# DAC.net
KiCad netlist of a schematic drawn in Altium Designer
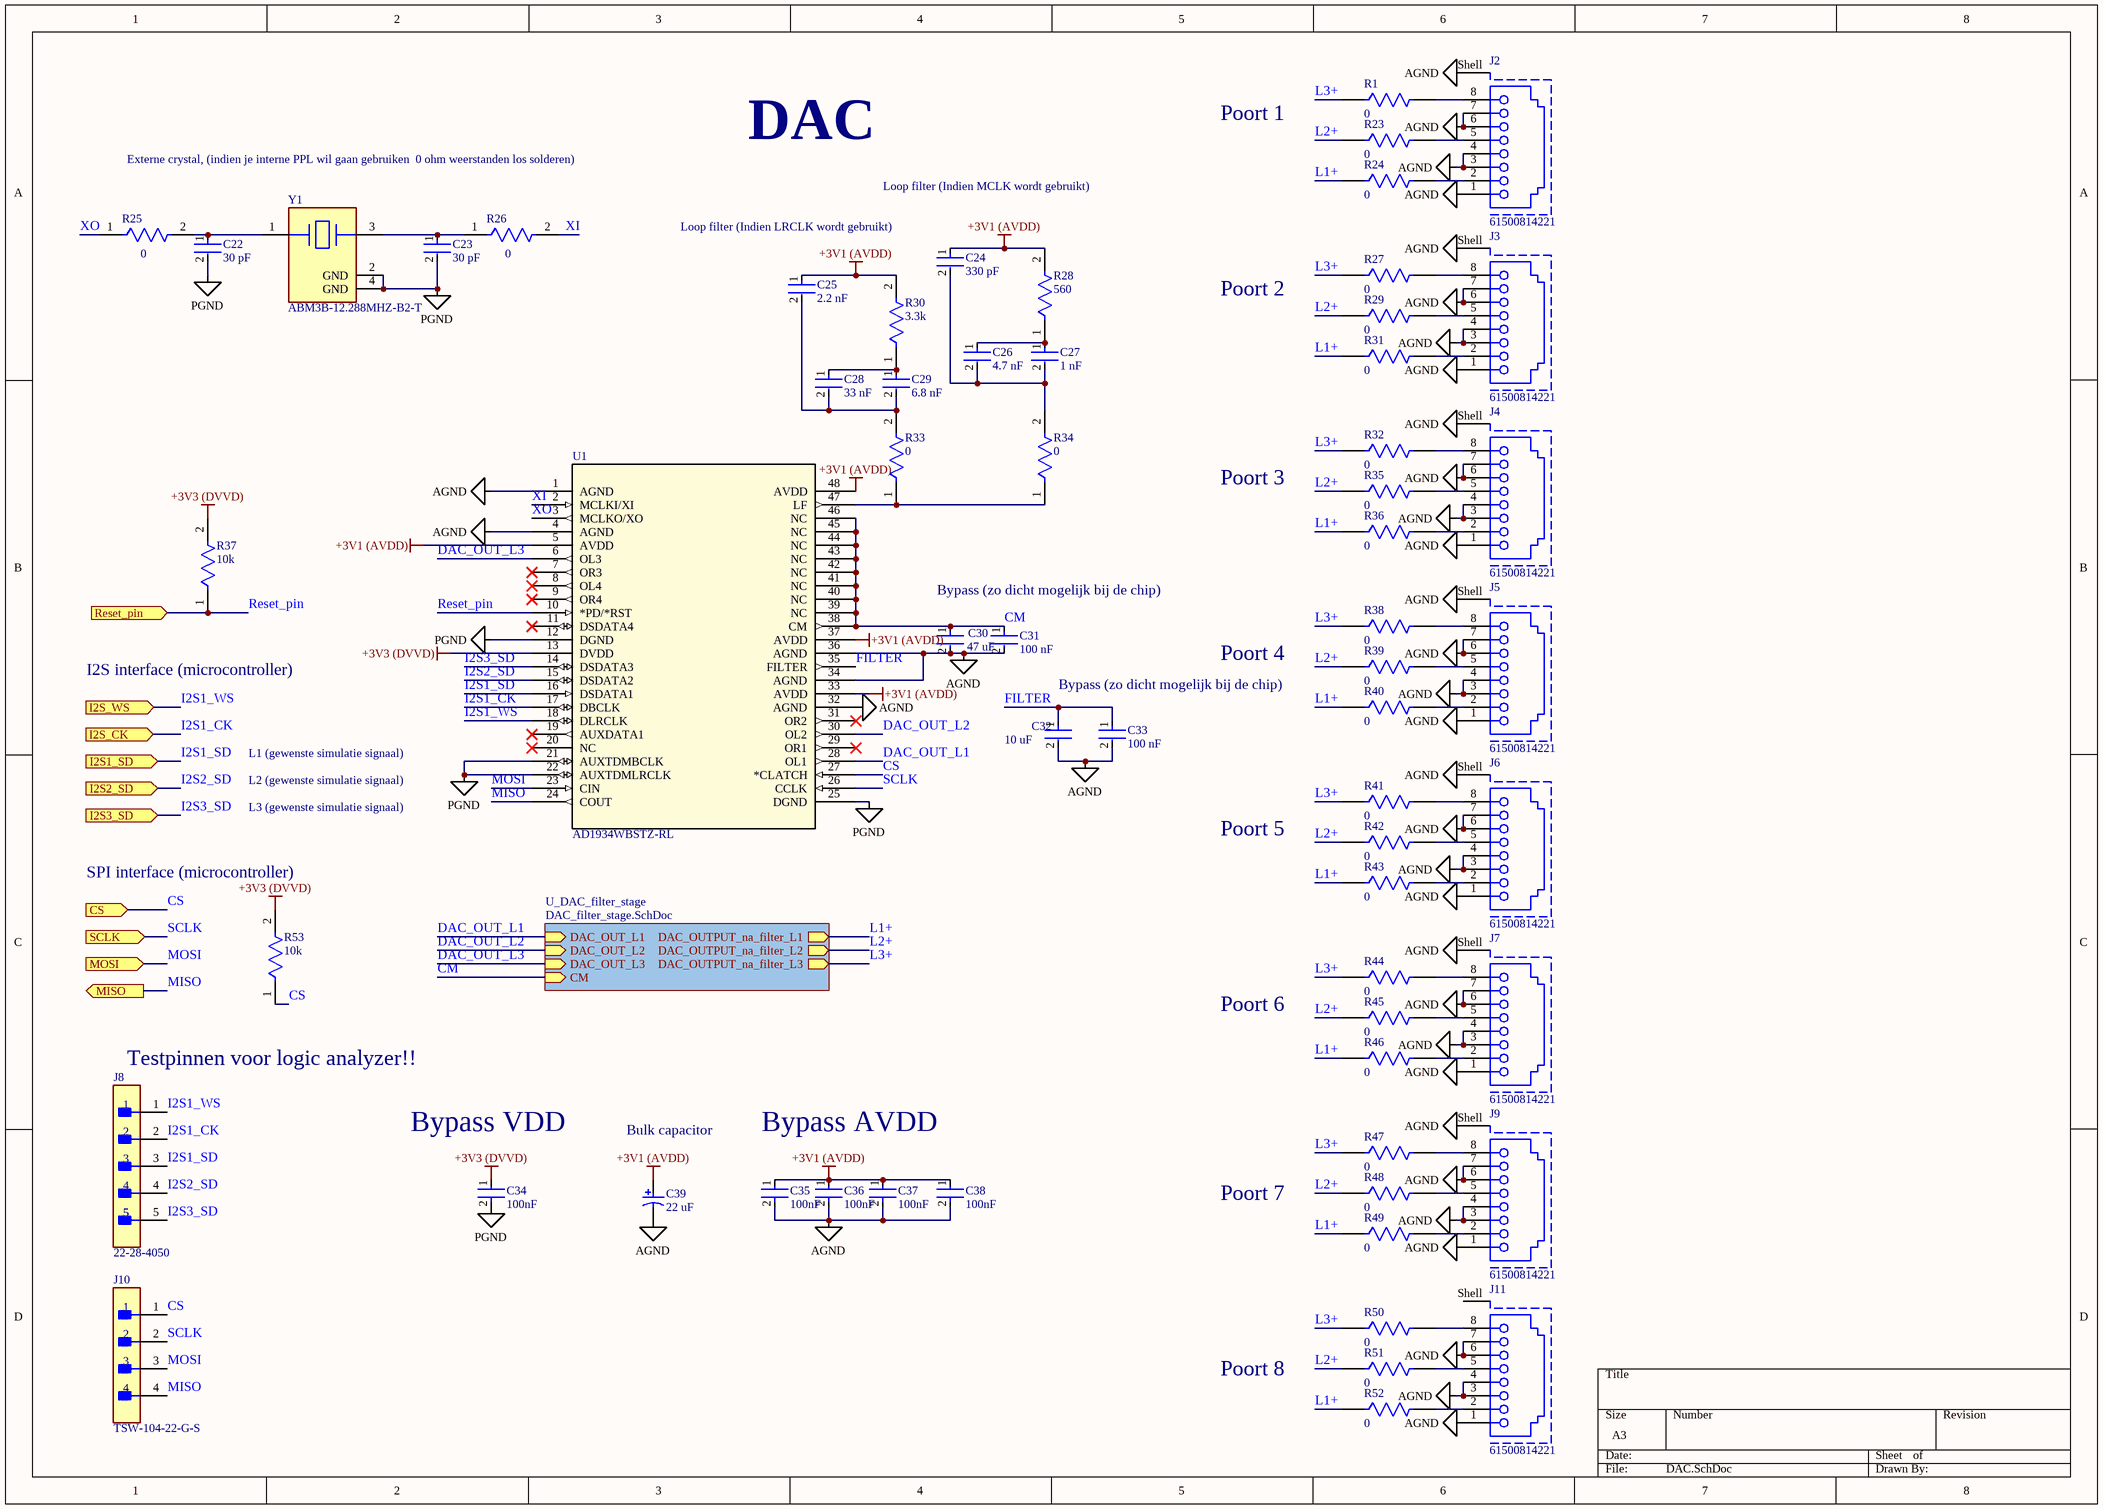
[diagram p0: DAC.SchDoc]

(export (version "E")
  (design (tool "Eeschema 10.0.6"))
  (components
    (comp (ref "C22")
      (value "30 pF")
      (footprint "FP-AC0603-MFG")
      (description "AC0603 30 pF NP0 5.00% 50 V")
      (fields
        (field (name "TOLERANCE") "0.05")
        (field (name "OCTOPART") "https://octopart.com/ac0603jrnpo9bn271-yageo-87214073")
      )
      (libsource (lib "Altium Content Vault") (part "11868f565c42a9108669ba33697ecf6"))
    )
    (comp (ref "C23")
      (value "30 pF")
      (footprint "FP-AC0603-MFG")
      (description "AC0603 30 pF NP0 5.00% 50 V")
      (fields
        (field (name "TOLERANCE") "0.05")
        (field (name "OCTOPART") "https://octopart.com/ac0603jrnpo9bn271-yageo-87214073")
      )
      (libsource (lib "Altium Content Vault") (part "11868f565c42a9108669ba33697ecf6"))
    )
    (comp (ref "C24")
      (value "330 pF")
      (footprint "FP-C0603C-CF-MFG")
      (description "CAP CER 330 pF 50V 5% X7R 0603")
      (fields (field (name "TOLERANCE") "0.05") (field (name "MANUFACTURER PART NUMBER") "C0603C104J5RACTU"))
      (libsource (lib "Altium Content Vault") (part "b4654b650e69147ec39a6b967a45e02"))
    )
    (comp (ref "C25")
      (value "2.2 nF")
      (footprint "FP-C0603C-CF-MFG")
      (description "CAP CER 2.2 nF 50V 5% X7R 0603")
      (fields (field (name "TOLERANCE") "0.05") (field (name "MANUFACTURER PART NUMBER") "C0603C104J5RACTU"))
      (libsource (lib "Altium Content Vault") (part "b4654b650e69147ec39a6b967a45e02"))
    )
    (comp (ref "C26")
      (value "4.7 nF")
      (footprint "FP-C0603C-CF-MFG")
      (description "CAP CER 33 nF 50V 5% X7R 0603")
      (fields (field (name "TOLERANCE") "0.05") (field (name "MANUFACTURER PART NUMBER") "C0603C104J5RACTU"))
      (libsource (lib "Altium Content Vault") (part "b4654b650e69147ec39a6b967a45e02"))
    )
    (comp (ref "C27")
      (value "1 nF")
      (footprint "FP-C0603C-CF-MFG")
      (description "CAP CER 1 nF 50V 5% X7R 0603")
      (fields (field (name "TOLERANCE") "0.05") (field (name "MANUFACTURER PART NUMBER") "C0603C104J5RACTU"))
      (libsource (lib "Altium Content Vault") (part "b4654b650e69147ec39a6b967a45e02"))
    )
    (comp (ref "C28")
      (value "33 nF")
      (footprint "FP-C0603C-CF-MFG")
      (description "CAP CER 33 nF 50V 5% X7R 0603")
      (fields (field (name "TOLERANCE") "0.05") (field (name "MANUFACTURER PART NUMBER") "C0603C104J5RACTU"))
      (libsource (lib "Altium Content Vault") (part "b4654b650e69147ec39a6b967a45e02"))
    )
    (comp (ref "C29")
      (value "6.8 nF")
      (footprint "FP-C0603C-CF-MFG")
      (description "CAP CER 6.8 nF 50V 5% X7R 0603")
      (fields (field (name "TOLERANCE") "0.05") (field (name "MANUFACTURER PART NUMBER") "C0603C104J5RACTU"))
      (libsource (lib "Altium Content Vault") (part "b4654b650e69147ec39a6b967a45e02"))
    )
    (comp (ref "C30")
      (value "47 uF")
      (footprint "FP-C0805C476M9PACTU-MFG")
      (description "CAP CER 47UF 6.3V X5R 0805")
      (fields (field (name "VOLTAGE") "6.3V") (field (name "TOLERANCE") "20%"))
      (libsource (lib "Altium Content Vault") (part "11868f565c42a9108669ba33697ecf6"))
    )
    (comp (ref "C31")
      (value "100 nF")
      (footprint "FP-C0603C-CF-MFG")
      (description "CAP CER 100 nF 50V 5% X7R 0603")
      (fields (field (name "TOLERANCE") "0.05") (field (name "MANUFACTURER PART NUMBER") "C0603C104J5RACTU"))
      (libsource (lib "Altium Content Vault") (part "b4654b650e69147ec39a6b967a45e02"))
    )
    (comp (ref "C32")
      (value "10 uF")
      (footprint "FP-C0603C-CF-MFG")
      (description "CAP CER 10 uF 50V 5% X7R 0603")
      (fields (field (name "TOLERANCE") "0.05") (field (name "MANUFACTURER PART NUMBER") "C0603C104J5RACTU"))
      (libsource (lib "Altium Content Vault") (part "b4654b650e69147ec39a6b967a45e02"))
    )
    (comp (ref "C33")
      (value "100 nF")
      (footprint "FP-C0603C-CF-MFG")
      (description "CAP CER 100 nF 50V 5% X7R 0603")
      (fields (field (name "TOLERANCE") "0.05") (field (name "MANUFACTURER PART NUMBER") "C0603C104J5RACTU"))
      (libsource (lib "Altium Content Vault") (part "b4654b650e69147ec39a6b967a45e02"))
    )
    (comp (ref "C34")
      (value "100nF")
      (footprint "FP-GRM15-MFG")
      (description "CAP CER 0.1UF 16V X7R 0402")
      (fields (field (name "MANUFACTURER PART NUMBER") "GRM155R71C104KA88D") (field (name "TOLERANCE") "10%"))
      (libsource (lib "Altium Content Vault") (part "236180d848d6139a670b325ea6854c9"))
    )
    (comp (ref "C35")
      (value "100nF")
      (footprint "FP-GRM15-MFG")
      (description "CAP CER 0.1UF 16V X7R 0402")
      (fields (field (name "MANUFACTURER PART NUMBER") "GRM155R71C104KA88D") (field (name "TOLERANCE") "10%"))
      (libsource (lib "Altium Content Vault") (part "236180d848d6139a670b325ea6854c9"))
    )
    (comp (ref "C36")
      (value "100nF")
      (footprint "FP-GRM15-MFG")
      (description "CAP CER 0.1UF 16V X7R 0402")
      (fields (field (name "MANUFACTURER PART NUMBER") "GRM155R71C104KA88D") (field (name "TOLERANCE") "10%"))
      (libsource (lib "Altium Content Vault") (part "236180d848d6139a670b325ea6854c9"))
    )
    (comp (ref "C37")
      (value "100nF")
      (footprint "FP-GRM15-MFG")
      (description "CAP CER 0.1UF 16V X7R 0402")
      (fields (field (name "MANUFACTURER PART NUMBER") "GRM155R71C104KA88D") (field (name "TOLERANCE") "10%"))
      (libsource (lib "Altium Content Vault") (part "236180d848d6139a670b325ea6854c9"))
    )
    (comp (ref "C38")
      (value "100nF")
      (footprint "FP-GRM15-MFG")
      (description "CAP CER 0.1UF 16V X7R 0402")
      (fields (field (name "MANUFACTURER PART NUMBER") "GRM155R71C104KA88D") (field (name "TOLERANCE") "10%"))
      (libsource (lib "Altium Content Vault") (part "236180d848d6139a670b325ea6854c9"))
    )
    (comp (ref "C39")
      (value "22 uF")
      (footprint "CAPPR55-200-1100X500X1200")
      (description "Aluminum Electrolytic Capacitor, 22 uF, +/- 20%, 50 V, -40 to 85 degC, 2-Pin THD, RoHS, Bulk")
      (fields (field (name "VOLTAGE") "50V") (field (name "MANUFACTURER") "Panasonic"))
      (libsource (lib "Altium Content Vault") (part "CAP-P-2"))
    )
    (comp (ref "J2")
      (value "61500814221")
      (footprint "61500814221")
      (libsource (lib "Altium Content Vault") (part "8P8C - 1 Port - Shielded"))
    )
    (comp (ref "J3")
      (value "61500814221")
      (footprint "61500814221")
      (libsource (lib "Altium Content Vault") (part "8P8C - 1 Port - Shielded"))
    )
    (comp (ref "J4")
      (value "61500814221")
      (footprint "61500814221")
      (libsource (lib "Altium Content Vault") (part "8P8C - 1 Port - Shielded"))
    )
    (comp (ref "J5")
      (value "61500814221")
      (footprint "61500814221")
      (libsource (lib "Altium Content Vault") (part "8P8C - 1 Port - Shielded"))
    )
    (comp (ref "J6")
      (value "61500814221")
      (footprint "61500814221")
      (libsource (lib "Altium Content Vault") (part "8P8C - 1 Port - Shielded"))
    )
    (comp (ref "J7")
      (value "61500814221")
      (footprint "61500814221")
      (libsource (lib "Altium Content Vault") (part "8P8C - 1 Port - Shielded"))
    )
    (comp (ref "J8")
      (value "22-28-4050")
      (footprint "FP-22-28-4050-MFG")
      (fields (field (name "GENERIC PART NUMBER") "GPHA-1X05"))
      (libsource (lib "Altium Content Vault") (part "bf93c07fd2649a848d0ec8585582aab"))
    )
    (comp (ref "J9")
      (value "61500814221")
      (footprint "61500814221")
      (libsource (lib "Altium Content Vault") (part "8P8C - 1 Port - Shielded"))
    )
    (comp (ref "J10")
      (value "TSW-104-22-G-S")
      (footprint "FP-TSW-104-22-G-S-MFG")
      (description "GENERIC PART NUMBER: GPHA-1X04\r\nCONN HEADER VERT 4POS 2.54MM")
      (fields (field (name "GENERIC PART NUMBER") "GPHA-1X04"))
      (libsource (lib "Altium Content Vault") (part "299a8cea1bdcbc3624fe62c390fa72c"))
    )
    (comp (ref "J11")
      (value "61500814221")
      (footprint "61500814221")
      (libsource (lib "Altium Content Vault") (part "8P8C - 1 Port - Shielded"))
    )
    (comp (ref "R1")
      (value "0")
      (footprint "FP-CRCW1206-MFG")
      (description "CRCW12060000ZSTA Zero Ohm Resistor, Jumper, 1206 [3216 Metric], Thick Film, 250 mW, Surface Mount")
      (libsource (lib "Altium Content Vault") (part "1029c3af85768c4190bb7ad29bc67b5"))
    )
    (comp (ref "R23")
      (value "0")
      (footprint "FP-CRCW1206-MFG")
      (description "CRCW12060000ZSTA Zero Ohm Resistor, Jumper, 1206 [3216 Metric], Thick Film, 250 mW, Surface Mount")
      (libsource (lib "Altium Content Vault") (part "1029c3af85768c4190bb7ad29bc67b5"))
    )
    (comp (ref "R24")
      (value "0")
      (footprint "FP-CRCW1206-MFG")
      (description "CRCW12060000ZSTA Zero Ohm Resistor, Jumper, 1206 [3216 Metric], Thick Film, 250 mW, Surface Mount")
      (libsource (lib "Altium Content Vault") (part "1029c3af85768c4190bb7ad29bc67b5"))
    )
    (comp (ref "R25")
      (value "0")
      (footprint "FP-CRCW1206-MFG")
      (description "CRCW12060000ZSTA Zero Ohm Resistor, Jumper, 1206 [3216 Metric], Thick Film, 250 mW, Surface Mount")
      (libsource (lib "") (part "1029c3af85768c4190bb7ad29bc67b5_1"))
    )
    (comp (ref "R26")
      (value "0")
      (footprint "FP-CRCW1206-MFG")
      (description "CRCW12060000ZSTA Zero Ohm Resistor, Jumper, 1206 [3216 Metric], Thick Film, 250 mW, Surface Mount")
      (libsource (lib "") (part "1029c3af85768c4190bb7ad29bc67b5_1"))
    )
    (comp (ref "R27")
      (value "0")
      (footprint "FP-CRCW1206-MFG")
      (description "CRCW12060000ZSTA Zero Ohm Resistor, Jumper, 1206 [3216 Metric], Thick Film, 250 mW, Surface Mount")
      (libsource (lib "Altium Content Vault") (part "1029c3af85768c4190bb7ad29bc67b5"))
    )
    (comp (ref "R28")
      (value "560")
      (footprint "FP-RC1608-IPC_B")
      (fields (field (name "TOLERANCE") "1%"))
      (libsource (lib "") (part "1029c3af85768c4190bb7ad29bc67b5_1"))
    )
    (comp (ref "R29")
      (value "0")
      (footprint "FP-CRCW1206-MFG")
      (description "CRCW12060000ZSTA Zero Ohm Resistor, Jumper, 1206 [3216 Metric], Thick Film, 250 mW, Surface Mount")
      (libsource (lib "Altium Content Vault") (part "1029c3af85768c4190bb7ad29bc67b5"))
    )
    (comp (ref "R30")
      (value "3.3k")
      (footprint "FP-RC1608-IPC_B")
      (fields (field (name "TOLERANCE") "1%"))
      (libsource (lib "") (part "1029c3af85768c4190bb7ad29bc67b5_1"))
    )
    (comp (ref "R31")
      (value "0")
      (footprint "FP-CRCW1206-MFG")
      (description "CRCW12060000ZSTA Zero Ohm Resistor, Jumper, 1206 [3216 Metric], Thick Film, 250 mW, Surface Mount")
      (libsource (lib "Altium Content Vault") (part "1029c3af85768c4190bb7ad29bc67b5"))
    )
    (comp (ref "R32")
      (value "0")
      (footprint "FP-CRCW1206-MFG")
      (description "CRCW12060000ZSTA Zero Ohm Resistor, Jumper, 1206 [3216 Metric], Thick Film, 250 mW, Surface Mount")
      (libsource (lib "Altium Content Vault") (part "1029c3af85768c4190bb7ad29bc67b5"))
    )
    (comp (ref "R33")
      (value "0")
      (footprint "FP-CRCW1206-MFG")
      (description "CRCW12060000ZSTA Zero Ohm Resistor, Jumper, 1206 [3216 Metric], Thick Film, 250 mW, Surface Mount")
      (libsource (lib "") (part "1029c3af85768c4190bb7ad29bc67b5_1"))
    )
    (comp (ref "R34")
      (value "0")
      (footprint "FP-CRCW1206-MFG")
      (description "CRCW12060000ZSTA Zero Ohm Resistor, Jumper, 1206 [3216 Metric], Thick Film, 250 mW, Surface Mount")
      (libsource (lib "") (part "1029c3af85768c4190bb7ad29bc67b5_1"))
    )
    (comp (ref "R35")
      (value "0")
      (footprint "FP-CRCW1206-MFG")
      (description "CRCW12060000ZSTA Zero Ohm Resistor, Jumper, 1206 [3216 Metric], Thick Film, 250 mW, Surface Mount")
      (libsource (lib "Altium Content Vault") (part "1029c3af85768c4190bb7ad29bc67b5"))
    )
    (comp (ref "R36")
      (value "0")
      (footprint "FP-CRCW1206-MFG")
      (description "CRCW12060000ZSTA Zero Ohm Resistor, Jumper, 1206 [3216 Metric], Thick Film, 250 mW, Surface Mount")
      (libsource (lib "Altium Content Vault") (part "1029c3af85768c4190bb7ad29bc67b5"))
    )
    (comp (ref "R37")
      (value "10k")
      (footprint "FP-RC1608-IPC_B")
      (fields (field (name "TOLERANCE") "1%"))
      (libsource (lib "") (part "1029c3af85768c4190bb7ad29bc67b5_1"))
    )
    (comp (ref "R38")
      (value "0")
      (footprint "FP-CRCW1206-MFG")
      (description "CRCW12060000ZSTA Zero Ohm Resistor, Jumper, 1206 [3216 Metric], Thick Film, 250 mW, Surface Mount")
      (libsource (lib "Altium Content Vault") (part "1029c3af85768c4190bb7ad29bc67b5"))
    )
    (comp (ref "R39")
      (value "0")
      (footprint "FP-CRCW1206-MFG")
      (description "CRCW12060000ZSTA Zero Ohm Resistor, Jumper, 1206 [3216 Metric], Thick Film, 250 mW, Surface Mount")
      (libsource (lib "Altium Content Vault") (part "1029c3af85768c4190bb7ad29bc67b5"))
    )
    (comp (ref "R40")
      (value "0")
      (footprint "FP-CRCW1206-MFG")
      (description "CRCW12060000ZSTA Zero Ohm Resistor, Jumper, 1206 [3216 Metric], Thick Film, 250 mW, Surface Mount")
      (libsource (lib "Altium Content Vault") (part "1029c3af85768c4190bb7ad29bc67b5"))
    )
    (comp (ref "R41")
      (value "0")
      (footprint "FP-CRCW1206-MFG")
      (description "CRCW12060000ZSTA Zero Ohm Resistor, Jumper, 1206 [3216 Metric], Thick Film, 250 mW, Surface Mount")
      (libsource (lib "Altium Content Vault") (part "1029c3af85768c4190bb7ad29bc67b5"))
    )
    (comp (ref "R42")
      (value "0")
      (footprint "FP-CRCW1206-MFG")
      (description "CRCW12060000ZSTA Zero Ohm Resistor, Jumper, 1206 [3216 Metric], Thick Film, 250 mW, Surface Mount")
      (libsource (lib "Altium Content Vault") (part "1029c3af85768c4190bb7ad29bc67b5"))
    )
    (comp (ref "R43")
      (value "0")
      (footprint "FP-CRCW1206-MFG")
      (description "CRCW12060000ZSTA Zero Ohm Resistor, Jumper, 1206 [3216 Metric], Thick Film, 250 mW, Surface Mount")
      (libsource (lib "Altium Content Vault") (part "1029c3af85768c4190bb7ad29bc67b5"))
    )
    (comp (ref "R44")
      (value "0")
      (footprint "FP-CRCW1206-MFG")
      (description "CRCW12060000ZSTA Zero Ohm Resistor, Jumper, 1206 [3216 Metric], Thick Film, 250 mW, Surface Mount")
      (libsource (lib "Altium Content Vault") (part "1029c3af85768c4190bb7ad29bc67b5"))
    )
    (comp (ref "R45")
      (value "0")
      (footprint "FP-CRCW1206-MFG")
      (description "CRCW12060000ZSTA Zero Ohm Resistor, Jumper, 1206 [3216 Metric], Thick Film, 250 mW, Surface Mount")
      (libsource (lib "Altium Content Vault") (part "1029c3af85768c4190bb7ad29bc67b5"))
    )
    (comp (ref "R46")
      (value "0")
      (footprint "FP-CRCW1206-MFG")
      (description "CRCW12060000ZSTA Zero Ohm Resistor, Jumper, 1206 [3216 Metric], Thick Film, 250 mW, Surface Mount")
      (libsource (lib "Altium Content Vault") (part "1029c3af85768c4190bb7ad29bc67b5"))
    )
    (comp (ref "R47")
      (value "0")
      (footprint "FP-CRCW1206-MFG")
      (description "CRCW12060000ZSTA Zero Ohm Resistor, Jumper, 1206 [3216 Metric], Thick Film, 250 mW, Surface Mount")
      (libsource (lib "Altium Content Vault") (part "1029c3af85768c4190bb7ad29bc67b5"))
    )
    (comp (ref "R48")
      (value "0")
      (footprint "FP-CRCW1206-MFG")
      (description "CRCW12060000ZSTA Zero Ohm Resistor, Jumper, 1206 [3216 Metric], Thick Film, 250 mW, Surface Mount")
      (libsource (lib "Altium Content Vault") (part "1029c3af85768c4190bb7ad29bc67b5"))
    )
    (comp (ref "R49")
      (value "0")
      (footprint "FP-CRCW1206-MFG")
      (description "CRCW12060000ZSTA Zero Ohm Resistor, Jumper, 1206 [3216 Metric], Thick Film, 250 mW, Surface Mount")
      (libsource (lib "Altium Content Vault") (part "1029c3af85768c4190bb7ad29bc67b5"))
    )
    (comp (ref "R50")
      (value "0")
      (footprint "FP-CRCW1206-MFG")
      (description "CRCW12060000ZSTA Zero Ohm Resistor, Jumper, 1206 [3216 Metric], Thick Film, 250 mW, Surface Mount")
      (libsource (lib "Altium Content Vault") (part "1029c3af85768c4190bb7ad29bc67b5"))
    )
    (comp (ref "R51")
      (value "0")
      (footprint "FP-CRCW1206-MFG")
      (description "CRCW12060000ZSTA Zero Ohm Resistor, Jumper, 1206 [3216 Metric], Thick Film, 250 mW, Surface Mount")
      (libsource (lib "Altium Content Vault") (part "1029c3af85768c4190bb7ad29bc67b5"))
    )
    (comp (ref "R52")
      (value "0")
      (footprint "FP-CRCW1206-MFG")
      (description "CRCW12060000ZSTA Zero Ohm Resistor, Jumper, 1206 [3216 Metric], Thick Film, 250 mW, Surface Mount")
      (libsource (lib "Altium Content Vault") (part "1029c3af85768c4190bb7ad29bc67b5"))
    )
    (comp (ref "R53")
      (value "10k")
      (footprint "FP-RC1608-IPC_B")
      (fields (field (name "TOLERANCE") "1%"))
      (libsource (lib "") (part "1029c3af85768c4190bb7ad29bc67b5_1"))
    )
    (comp (ref "U1")
      (value "AD1934WBSTZ-RL")
      (footprint "ST_48_ADI")
      (description "No Description Available")
      (libsource (lib "AD1934WBSTZ-RL") (part "AD1934WBSTZ-RL"))
    )
    (comp (ref "Y1")
      (value "ABM3B-12.288MHZ-B2-T")
      (footprint "FP-ABM3B-MFG")
      (description "Crystal 12.288MHz ±20ppm 18pF SMD-4 5mm x 3.2mm")
      (fields (field (name "TOLERANCE") "20ppm"))
      (libsource (lib "Altium Content Vault") (part "48e526d86b7f2615d98721063c72f49"))
    )
  )
  (nets
    (net (code "1") (name "+3V1 (AVDD)") (class "Default")
      (node (ref "C24") (pin "1") (pinfunction "1_1") (pintype "passive"))
      (node (ref "C25") (pin "1") (pinfunction "1_1") (pintype "passive"))
      (node (ref "C35") (pin "1") (pinfunction "1_1") (pintype "passive"))
      (node (ref "C36") (pin "1") (pinfunction "1_1") (pintype "passive"))
      (node (ref "C37") (pin "1") (pinfunction "1_1") (pintype "passive"))
      (node (ref "C38") (pin "1") (pinfunction "1_1") (pintype "passive"))
      (node (ref "C39") (pin "1") (pinfunction "1_1") (pintype "passive"))
      (node (ref "R28") (pin "2") (pinfunction "2_2") (pintype "passive"))
      (node (ref "R30") (pin "2") (pinfunction "2_2") (pintype "passive"))
      (node (ref "U1") (pin "33") (pinfunction "AVDD_33") (pintype "power_in"))
      (node (ref "U1") (pin "37") (pinfunction "AVDD_37") (pintype "power_in"))
      (node (ref "U1") (pin "48") (pinfunction "AVDD_48") (pintype "power_in"))
      (node (ref "U1") (pin "5") (pinfunction "AVDD_5") (pintype "power_in"))
    )
    (net (code "2") (name "+3V3 (DVVD)") (class "Default")
      (node (ref "C34") (pin "1") (pinfunction "1_1") (pintype "passive"))
      (node (ref "R37") (pin "2") (pinfunction "2_2") (pintype "passive"))
      (node (ref "R53") (pin "2") (pinfunction "2_2") (pintype "passive"))
      (node (ref "U1") (pin "13") (pinfunction "DVDD_13") (pintype "power_in"))
    )
    (net (code "3") (name "/CM") (class "Default")
      (node (ref "C30") (pin "1") (pinfunction "1_1") (pintype "passive"))
      (node (ref "C31") (pin "1") (pinfunction "1_1") (pintype "passive"))
      (node (ref "U1") (pin "38") (pinfunction "CM_38") (pintype "output"))
      (node (ref "U1") (pin "39") (pinfunction "NC_39") (pintype "passive"))
      (node (ref "U1") (pin "40") (pinfunction "NC_40") (pintype "passive"))
      (node (ref "U1") (pin "41") (pinfunction "NC_41") (pintype "passive"))
      (node (ref "U1") (pin "42") (pinfunction "NC_42") (pintype "passive"))
      (node (ref "U1") (pin "43") (pinfunction "NC_43") (pintype "passive"))
      (node (ref "U1") (pin "44") (pinfunction "NC_44") (pintype "passive"))
      (node (ref "U1") (pin "45") (pinfunction "NC_45") (pintype "passive"))
      (node (ref "U1") (pin "46") (pinfunction "NC_46") (pintype "passive"))
    )
    (net (code "4") (name "/CS") (class "Default")
      (node (ref "J10") (pin "1") (pinfunction "1_1") (pintype "passive"))
      (node (ref "R53") (pin "1") (pinfunction "1_1") (pintype "passive"))
      (node (ref "U1") (pin "27") (pinfunction "*CLATCH_27") (pintype "input"))
    )
    (net (code "5") (name "/DAC_OUT_L1") (class "Default")
      (node (ref "U1") (pin "28") (pinfunction "OL1_28") (pintype "output"))
    )
    (net (code "6") (name "/DAC_OUT_L2") (class "Default")
      (node (ref "U1") (pin "30") (pinfunction "OL2_30") (pintype "output"))
    )
    (net (code "7") (name "/DAC_OUT_L3") (class "Default")
      (node (ref "U1") (pin "6") (pinfunction "OL3_6") (pintype "output"))
    )
    (net (code "8") (name "/FILTER") (class "Default")
      (node (ref "C32") (pin "1") (pinfunction "1_1") (pintype "passive"))
      (node (ref "C33") (pin "1") (pinfunction "1_1") (pintype "passive"))
      (node (ref "U1") (pin "35") (pinfunction "FILTER_35") (pintype "output"))
    )
    (net (code "9") (name "/I2S1_CK") (class "Default")
      (node (ref "J8") (pin "2") (pinfunction "2_2") (pintype "passive"))
      (node (ref "U1") (pin "17") (pinfunction "DBCLK_17") (pintype "bidirectional"))
    )
    (net (code "10") (name "/I2S1_SD") (class "Default")
      (node (ref "J8") (pin "3") (pinfunction "3_3") (pintype "passive"))
      (node (ref "U1") (pin "16") (pinfunction "DSDATA1_16") (pintype "input"))
    )
    (net (code "11") (name "/I2S1_WS") (class "Default")
      (node (ref "J8") (pin "1") (pinfunction "1_1") (pintype "passive"))
      (node (ref "U1") (pin "18") (pinfunction "DLRCLK_18") (pintype "bidirectional"))
    )
    (net (code "12") (name "/I2S2_SD") (class "Default")
      (node (ref "J8") (pin "4") (pinfunction "4_4") (pintype "passive"))
      (node (ref "U1") (pin "15") (pinfunction "DSDATA2_15") (pintype "bidirectional"))
    )
    (net (code "13") (name "/I2S3_SD") (class "Default")
      (node (ref "J8") (pin "5") (pinfunction "5_5") (pintype "passive"))
      (node (ref "U1") (pin "14") (pinfunction "DSDATA3_14") (pintype "bidirectional"))
    )
    (net (code "14") (name "/L1+") (class "Default")
      (node (ref "R24") (pin "1") (pinfunction "1_1") (pintype "passive"))
      (node (ref "R31") (pin "1") (pinfunction "1_1") (pintype "passive"))
      (node (ref "R36") (pin "1") (pinfunction "1_1") (pintype "passive"))
      (node (ref "R40") (pin "1") (pinfunction "1_1") (pintype "passive"))
      (node (ref "R43") (pin "1") (pinfunction "1_1") (pintype "passive"))
      (node (ref "R46") (pin "1") (pinfunction "1_1") (pintype "passive"))
      (node (ref "R49") (pin "1") (pinfunction "1_1") (pintype "passive"))
      (node (ref "R52") (pin "1") (pinfunction "1_1") (pintype "passive"))
    )
    (net (code "15") (name "/L2+") (class "Default")
      (node (ref "R23") (pin "1") (pinfunction "1_1") (pintype "passive"))
      (node (ref "R29") (pin "1") (pinfunction "1_1") (pintype "passive"))
      (node (ref "R35") (pin "1") (pinfunction "1_1") (pintype "passive"))
      (node (ref "R39") (pin "1") (pinfunction "1_1") (pintype "passive"))
      (node (ref "R42") (pin "1") (pinfunction "1_1") (pintype "passive"))
      (node (ref "R45") (pin "1") (pinfunction "1_1") (pintype "passive"))
      (node (ref "R48") (pin "1") (pinfunction "1_1") (pintype "passive"))
      (node (ref "R51") (pin "1") (pinfunction "1_1") (pintype "passive"))
    )
    (net (code "16") (name "/L3+") (class "Default")
      (node (ref "R1") (pin "1") (pinfunction "1_1") (pintype "passive"))
      (node (ref "R27") (pin "1") (pinfunction "1_1") (pintype "passive"))
      (node (ref "R32") (pin "1") (pinfunction "1_1") (pintype "passive"))
      (node (ref "R38") (pin "1") (pinfunction "1_1") (pintype "passive"))
      (node (ref "R41") (pin "1") (pinfunction "1_1") (pintype "passive"))
      (node (ref "R44") (pin "1") (pinfunction "1_1") (pintype "passive"))
      (node (ref "R47") (pin "1") (pinfunction "1_1") (pintype "passive"))
      (node (ref "R50") (pin "1") (pinfunction "1_1") (pintype "passive"))
    )
    (net (code "17") (name "/MISO") (class "Default")
      (node (ref "J10") (pin "4") (pinfunction "4_4") (pintype "passive"))
      (node (ref "U1") (pin "24") (pinfunction "COUT_24") (pintype "output"))
    )
    (net (code "18") (name "/MOSI") (class "Default")
      (node (ref "J10") (pin "3") (pinfunction "3_3") (pintype "passive"))
      (node (ref "U1") (pin "23") (pinfunction "CIN_23") (pintype "input"))
    )
    (net (code "19") (name "/Reset_pin") (class "Default")
      (node (ref "R37") (pin "1") (pinfunction "1_1") (pintype "passive"))
      (node (ref "U1") (pin "10") (pinfunction "*PD/*RST_10") (pintype "input"))
    )
    (net (code "20") (name "/SCLK") (class "Default")
      (node (ref "J10") (pin "2") (pinfunction "2_2") (pintype "passive"))
      (node (ref "U1") (pin "26") (pinfunction "CCLK_26") (pintype "input"))
    )
    (net (code "21") (name "/XI") (class "Default")
      (node (ref "R26") (pin "2") (pinfunction "2_2") (pintype "passive"))
      (node (ref "U1") (pin "2") (pinfunction "MCLKI/XI_2") (pintype "input"))
    )
    (net (code "22") (name "/XO") (class "Default")
      (node (ref "R25") (pin "1") (pinfunction "1_1") (pintype "passive"))
      (node (ref "U1") (pin "3") (pinfunction "MCLKO/XO_3") (pintype "output"))
    )
    (net (code "23") (name "AGND") (class "Default")
      (node (ref "C30") (pin "2") (pinfunction "2_2") (pintype "passive"))
      (node (ref "C31") (pin "2") (pinfunction "2_2") (pintype "passive"))
      (node (ref "C32") (pin "2") (pinfunction "2_2") (pintype "passive"))
      (node (ref "C33") (pin "2") (pinfunction "2_2") (pintype "passive"))
      (node (ref "C35") (pin "2") (pinfunction "2_2") (pintype "passive"))
      (node (ref "C36") (pin "2") (pinfunction "2_2") (pintype "passive"))
      (node (ref "C37") (pin "2") (pinfunction "2_2") (pintype "passive"))
      (node (ref "C38") (pin "2") (pinfunction "2_2") (pintype "passive"))
      (node (ref "C39") (pin "2") (pinfunction "2_2") (pintype "passive"))
      (node (ref "J11") (pin "1") (pinfunction "1_1") (pintype "passive"))
      (node (ref "J11") (pin "3") (pinfunction "3_3") (pintype "passive"))
      (node (ref "J11") (pin "4") (pinfunction "4_4") (pintype "passive"))
      (node (ref "J11") (pin "6") (pinfunction "6_6") (pintype "passive"))
      (node (ref "J11") (pin "7") (pinfunction "7_7") (pintype "passive"))
      (node (ref "J2") (pin "1") (pinfunction "1_1") (pintype "passive"))
      (node (ref "J2") (pin "3") (pinfunction "3_3") (pintype "passive"))
      (node (ref "J2") (pin "4") (pinfunction "4_4") (pintype "passive"))
      (node (ref "J2") (pin "6") (pinfunction "6_6") (pintype "passive"))
      (node (ref "J2") (pin "7") (pinfunction "7_7") (pintype "passive"))
      (node (ref "J2") (pin "Shell") (pinfunction "Shell_Shell") (pintype "passive"))
      (node (ref "J3") (pin "1") (pinfunction "1_1") (pintype "passive"))
      (node (ref "J3") (pin "3") (pinfunction "3_3") (pintype "passive"))
      (node (ref "J3") (pin "4") (pinfunction "4_4") (pintype "passive"))
      (node (ref "J3") (pin "6") (pinfunction "6_6") (pintype "passive"))
      (node (ref "J3") (pin "7") (pinfunction "7_7") (pintype "passive"))
      (node (ref "J3") (pin "Shell") (pinfunction "Shell_Shell") (pintype "passive"))
      (node (ref "J4") (pin "1") (pinfunction "1_1") (pintype "passive"))
      (node (ref "J4") (pin "3") (pinfunction "3_3") (pintype "passive"))
      (node (ref "J4") (pin "4") (pinfunction "4_4") (pintype "passive"))
      (node (ref "J4") (pin "6") (pinfunction "6_6") (pintype "passive"))
      (node (ref "J4") (pin "7") (pinfunction "7_7") (pintype "passive"))
      (node (ref "J4") (pin "Shell") (pinfunction "Shell_Shell") (pintype "passive"))
      (node (ref "J5") (pin "1") (pinfunction "1_1") (pintype "passive"))
      (node (ref "J5") (pin "3") (pinfunction "3_3") (pintype "passive"))
      (node (ref "J5") (pin "4") (pinfunction "4_4") (pintype "passive"))
      (node (ref "J5") (pin "6") (pinfunction "6_6") (pintype "passive"))
      (node (ref "J5") (pin "7") (pinfunction "7_7") (pintype "passive"))
      (node (ref "J5") (pin "Shell") (pinfunction "Shell_Shell") (pintype "passive"))
      (node (ref "J6") (pin "1") (pinfunction "1_1") (pintype "passive"))
      (node (ref "J6") (pin "3") (pinfunction "3_3") (pintype "passive"))
      (node (ref "J6") (pin "4") (pinfunction "4_4") (pintype "passive"))
      (node (ref "J6") (pin "6") (pinfunction "6_6") (pintype "passive"))
      (node (ref "J6") (pin "7") (pinfunction "7_7") (pintype "passive"))
      (node (ref "J6") (pin "Shell") (pinfunction "Shell_Shell") (pintype "passive"))
      (node (ref "J7") (pin "1") (pinfunction "1_1") (pintype "passive"))
      (node (ref "J7") (pin "3") (pinfunction "3_3") (pintype "passive"))
      (node (ref "J7") (pin "4") (pinfunction "4_4") (pintype "passive"))
      (node (ref "J7") (pin "6") (pinfunction "6_6") (pintype "passive"))
      (node (ref "J7") (pin "7") (pinfunction "7_7") (pintype "passive"))
      (node (ref "J7") (pin "Shell") (pinfunction "Shell_Shell") (pintype "passive"))
      (node (ref "J9") (pin "1") (pinfunction "1_1") (pintype "passive"))
      (node (ref "J9") (pin "3") (pinfunction "3_3") (pintype "passive"))
      (node (ref "J9") (pin "4") (pinfunction "4_4") (pintype "passive"))
      (node (ref "J9") (pin "6") (pinfunction "6_6") (pintype "passive"))
      (node (ref "J9") (pin "7") (pinfunction "7_7") (pintype "passive"))
      (node (ref "J9") (pin "Shell") (pinfunction "Shell_Shell") (pintype "passive"))
      (node (ref "U1") (pin "1") (pinfunction "AGND_1") (pintype "power_in"))
      (node (ref "U1") (pin "32") (pinfunction "AGND_32") (pintype "power_in"))
      (node (ref "U1") (pin "34") (pinfunction "AGND_34") (pintype "power_in"))
      (node (ref "U1") (pin "36") (pinfunction "AGND_36") (pintype "power_in"))
      (node (ref "U1") (pin "4") (pinfunction "AGND_4") (pintype "power_in"))
    )
    (net (code "24") (name "Net-(C22-Pad1)") (class "Default")
      (node (ref "C22") (pin "1") (pinfunction "1_1") (pintype "passive"))
      (node (ref "R25") (pin "2") (pinfunction "2_2") (pintype "passive"))
      (node (ref "Y1") (pin "1") (pinfunction "1_1") (pintype "passive"))
    )
    (net (code "25") (name "Net-(C23-Pad1)") (class "Default")
      (node (ref "C23") (pin "1") (pinfunction "1_1") (pintype "passive"))
      (node (ref "R26") (pin "1") (pinfunction "1_1") (pintype "passive"))
      (node (ref "Y1") (pin "3") (pinfunction "3_3") (pintype "passive"))
    )
    (net (code "26") (name "Net-(C24-Pad2)") (class "Default")
      (node (ref "C24") (pin "2") (pinfunction "2_2") (pintype "passive"))
      (node (ref "C26") (pin "2") (pinfunction "2_2") (pintype "passive"))
      (node (ref "C27") (pin "2") (pinfunction "2_2") (pintype "passive"))
      (node (ref "R34") (pin "2") (pinfunction "2_2") (pintype "passive"))
    )
    (net (code "27") (name "Net-(C25-Pad2)") (class "Default")
      (node (ref "C25") (pin "2") (pinfunction "2_2") (pintype "passive"))
      (node (ref "C28") (pin "2") (pinfunction "2_2") (pintype "passive"))
      (node (ref "C29") (pin "2") (pinfunction "2_2") (pintype "passive"))
      (node (ref "R33") (pin "2") (pinfunction "2_2") (pintype "passive"))
    )
    (net (code "28") (name "Net-(C26-Pad1)") (class "Default")
      (node (ref "C26") (pin "1") (pinfunction "1_1") (pintype "passive"))
      (node (ref "C27") (pin "1") (pinfunction "1_1") (pintype "passive"))
      (node (ref "R28") (pin "1") (pinfunction "1_1") (pintype "passive"))
    )
    (net (code "29") (name "Net-(C28-Pad1)") (class "Default")
      (node (ref "C28") (pin "1") (pinfunction "1_1") (pintype "passive"))
      (node (ref "C29") (pin "1") (pinfunction "1_1") (pintype "passive"))
      (node (ref "R30") (pin "1") (pinfunction "1_1") (pintype "passive"))
    )
    (net (code "30") (name "Net-(J2-Pad2)") (class "Default")
      (node (ref "J2") (pin "2") (pinfunction "2_2") (pintype "passive"))
      (node (ref "R24") (pin "2") (pinfunction "2_2") (pintype "passive"))
    )
    (net (code "31") (name "Net-(J2-Pad5)") (class "Default")
      (node (ref "J2") (pin "5") (pinfunction "5_5") (pintype "passive"))
      (node (ref "R23") (pin "2") (pinfunction "2_2") (pintype "passive"))
    )
    (net (code "32") (name "Net-(J2-Pad8)") (class "Default")
      (node (ref "J2") (pin "8") (pinfunction "8_8") (pintype "passive"))
      (node (ref "R1") (pin "2") (pinfunction "2_2") (pintype "passive"))
    )
    (net (code "33") (name "Net-(J3-Pad2)") (class "Default")
      (node (ref "J3") (pin "2") (pinfunction "2_2") (pintype "passive"))
      (node (ref "R31") (pin "2") (pinfunction "2_2") (pintype "passive"))
    )
    (net (code "34") (name "Net-(J3-Pad5)") (class "Default")
      (node (ref "J3") (pin "5") (pinfunction "5_5") (pintype "passive"))
      (node (ref "R29") (pin "2") (pinfunction "2_2") (pintype "passive"))
    )
    (net (code "35") (name "Net-(J3-Pad8)") (class "Default")
      (node (ref "J3") (pin "8") (pinfunction "8_8") (pintype "passive"))
      (node (ref "R27") (pin "2") (pinfunction "2_2") (pintype "passive"))
    )
    (net (code "36") (name "Net-(J4-Pad2)") (class "Default")
      (node (ref "J4") (pin "2") (pinfunction "2_2") (pintype "passive"))
      (node (ref "R36") (pin "2") (pinfunction "2_2") (pintype "passive"))
    )
    (net (code "37") (name "Net-(J4-Pad5)") (class "Default")
      (node (ref "J4") (pin "5") (pinfunction "5_5") (pintype "passive"))
      (node (ref "R35") (pin "2") (pinfunction "2_2") (pintype "passive"))
    )
    (net (code "38") (name "Net-(J4-Pad8)") (class "Default")
      (node (ref "J4") (pin "8") (pinfunction "8_8") (pintype "passive"))
      (node (ref "R32") (pin "2") (pinfunction "2_2") (pintype "passive"))
    )
    (net (code "39") (name "Net-(J5-Pad2)") (class "Default")
      (node (ref "J5") (pin "2") (pinfunction "2_2") (pintype "passive"))
      (node (ref "R40") (pin "2") (pinfunction "2_2") (pintype "passive"))
    )
    (net (code "40") (name "Net-(J5-Pad5)") (class "Default")
      (node (ref "J5") (pin "5") (pinfunction "5_5") (pintype "passive"))
      (node (ref "R39") (pin "2") (pinfunction "2_2") (pintype "passive"))
    )
    (net (code "41") (name "Net-(J5-Pad8)") (class "Default")
      (node (ref "J5") (pin "8") (pinfunction "8_8") (pintype "passive"))
      (node (ref "R38") (pin "2") (pinfunction "2_2") (pintype "passive"))
    )
    (net (code "42") (name "Net-(J6-Pad2)") (class "Default")
      (node (ref "J6") (pin "2") (pinfunction "2_2") (pintype "passive"))
      (node (ref "R43") (pin "2") (pinfunction "2_2") (pintype "passive"))
    )
    (net (code "43") (name "Net-(J6-Pad5)") (class "Default")
      (node (ref "J6") (pin "5") (pinfunction "5_5") (pintype "passive"))
      (node (ref "R42") (pin "2") (pinfunction "2_2") (pintype "passive"))
    )
    (net (code "44") (name "Net-(J6-Pad8)") (class "Default")
      (node (ref "J6") (pin "8") (pinfunction "8_8") (pintype "passive"))
      (node (ref "R41") (pin "2") (pinfunction "2_2") (pintype "passive"))
    )
    (net (code "45") (name "Net-(J7-Pad2)") (class "Default")
      (node (ref "J7") (pin "2") (pinfunction "2_2") (pintype "passive"))
      (node (ref "R46") (pin "2") (pinfunction "2_2") (pintype "passive"))
    )
    (net (code "46") (name "Net-(J7-Pad5)") (class "Default")
      (node (ref "J7") (pin "5") (pinfunction "5_5") (pintype "passive"))
      (node (ref "R45") (pin "2") (pinfunction "2_2") (pintype "passive"))
    )
    (net (code "47") (name "Net-(J7-Pad8)") (class "Default")
      (node (ref "J7") (pin "8") (pinfunction "8_8") (pintype "passive"))
      (node (ref "R44") (pin "2") (pinfunction "2_2") (pintype "passive"))
    )
    (net (code "48") (name "Net-(J9-Pad2)") (class "Default")
      (node (ref "J9") (pin "2") (pinfunction "2_2") (pintype "passive"))
      (node (ref "R49") (pin "2") (pinfunction "2_2") (pintype "passive"))
    )
    (net (code "49") (name "Net-(J9-Pad5)") (class "Default")
      (node (ref "J9") (pin "5") (pinfunction "5_5") (pintype "passive"))
      (node (ref "R48") (pin "2") (pinfunction "2_2") (pintype "passive"))
    )
    (net (code "50") (name "Net-(J9-Pad8)") (class "Default")
      (node (ref "J9") (pin "8") (pinfunction "8_8") (pintype "passive"))
      (node (ref "R47") (pin "2") (pinfunction "2_2") (pintype "passive"))
    )
    (net (code "51") (name "Net-(J11-Pad2)") (class "Default")
      (node (ref "J11") (pin "2") (pinfunction "2_2") (pintype "passive"))
      (node (ref "R52") (pin "2") (pinfunction "2_2") (pintype "passive"))
    )
    (net (code "52") (name "Net-(J11-Pad5)") (class "Default")
      (node (ref "J11") (pin "5") (pinfunction "5_5") (pintype "passive"))
      (node (ref "R51") (pin "2") (pinfunction "2_2") (pintype "passive"))
    )
    (net (code "53") (name "Net-(J11-Pad8)") (class "Default")
      (node (ref "J11") (pin "8") (pinfunction "8_8") (pintype "passive"))
      (node (ref "R50") (pin "2") (pinfunction "2_2") (pintype "passive"))
    )
    (net (code "54") (name "Net-(U1-LF)") (class "Default")
      (node (ref "R33") (pin "1") (pinfunction "1_1") (pintype "passive"))
      (node (ref "R34") (pin "1") (pinfunction "1_1") (pintype "passive"))
      (node (ref "U1") (pin "47") (pinfunction "LF_47") (pintype "output"))
    )
    (net (code "55") (name "PGND") (class "Default")
      (node (ref "C22") (pin "2") (pinfunction "2_2") (pintype "passive"))
      (node (ref "C23") (pin "2") (pinfunction "2_2") (pintype "passive"))
      (node (ref "C34") (pin "2") (pinfunction "2_2") (pintype "passive"))
      (node (ref "U1") (pin "12") (pinfunction "DGND_12") (pintype "power_in"))
      (node (ref "U1") (pin "21") (pinfunction "AUXTDMBCLK_21") (pintype "bidirectional"))
      (node (ref "U1") (pin "22") (pinfunction "AUXTDMLRCLK_22") (pintype "bidirectional"))
      (node (ref "U1") (pin "25") (pinfunction "DGND_25") (pintype "power_in"))
      (node (ref "Y1") (pin "2") (pinfunction "GND_2") (pintype "power_in"))
      (node (ref "Y1") (pin "4") (pinfunction "GND_4") (pintype "power_in"))
    )
    (net (code "56") (name "unconnected-(J11-PadShell)") (class "Default")
      (node (ref "J11") (pin "Shell") (pinfunction "Shell_Shell") (pintype "passive"))
    )
    (net (code "57") (name "unconnected-(U1-AUXDATA1-Pad19)") (class "Default")
      (node (ref "U1") (pin "19") (pinfunction "AUXDATA1_19") (pintype "output+no_connect"))
    )
    (net (code "58") (name "unconnected-(U1-DSDATA4-Pad11)") (class "Default")
      (node (ref "U1") (pin "11") (pinfunction "DSDATA4_11") (pintype "bidirectional+no_connect"))
    )
    (net (code "59") (name "unconnected-(U1-NC-Pad20)") (class "Default")
      (node (ref "U1") (pin "20") (pinfunction "NC_20") (pintype "passive+no_connect"))
    )
    (net (code "60") (name "unconnected-(U1-OL4-Pad8)") (class "Default")
      (node (ref "U1") (pin "8") (pinfunction "OL4_8") (pintype "output+no_connect"))
    )
    (net (code "61") (name "unconnected-(U1-OR1-Pad29)") (class "Default")
      (node (ref "U1") (pin "29") (pinfunction "OR1_29") (pintype "output+no_connect"))
    )
    (net (code "62") (name "unconnected-(U1-OR2-Pad31)") (class "Default")
      (node (ref "U1") (pin "31") (pinfunction "OR2_31") (pintype "output+no_connect"))
    )
    (net (code "63") (name "unconnected-(U1-OR3-Pad7)") (class "Default")
      (node (ref "U1") (pin "7") (pinfunction "OR3_7") (pintype "output+no_connect"))
    )
    (net (code "64") (name "unconnected-(U1-OR4-Pad9)") (class "Default")
      (node (ref "U1") (pin "9") (pinfunction "OR4_9") (pintype "output+no_connect"))
    )
  )
)
